# Schematic.net
KiCad netlist of a schematic drawn in EAGLE
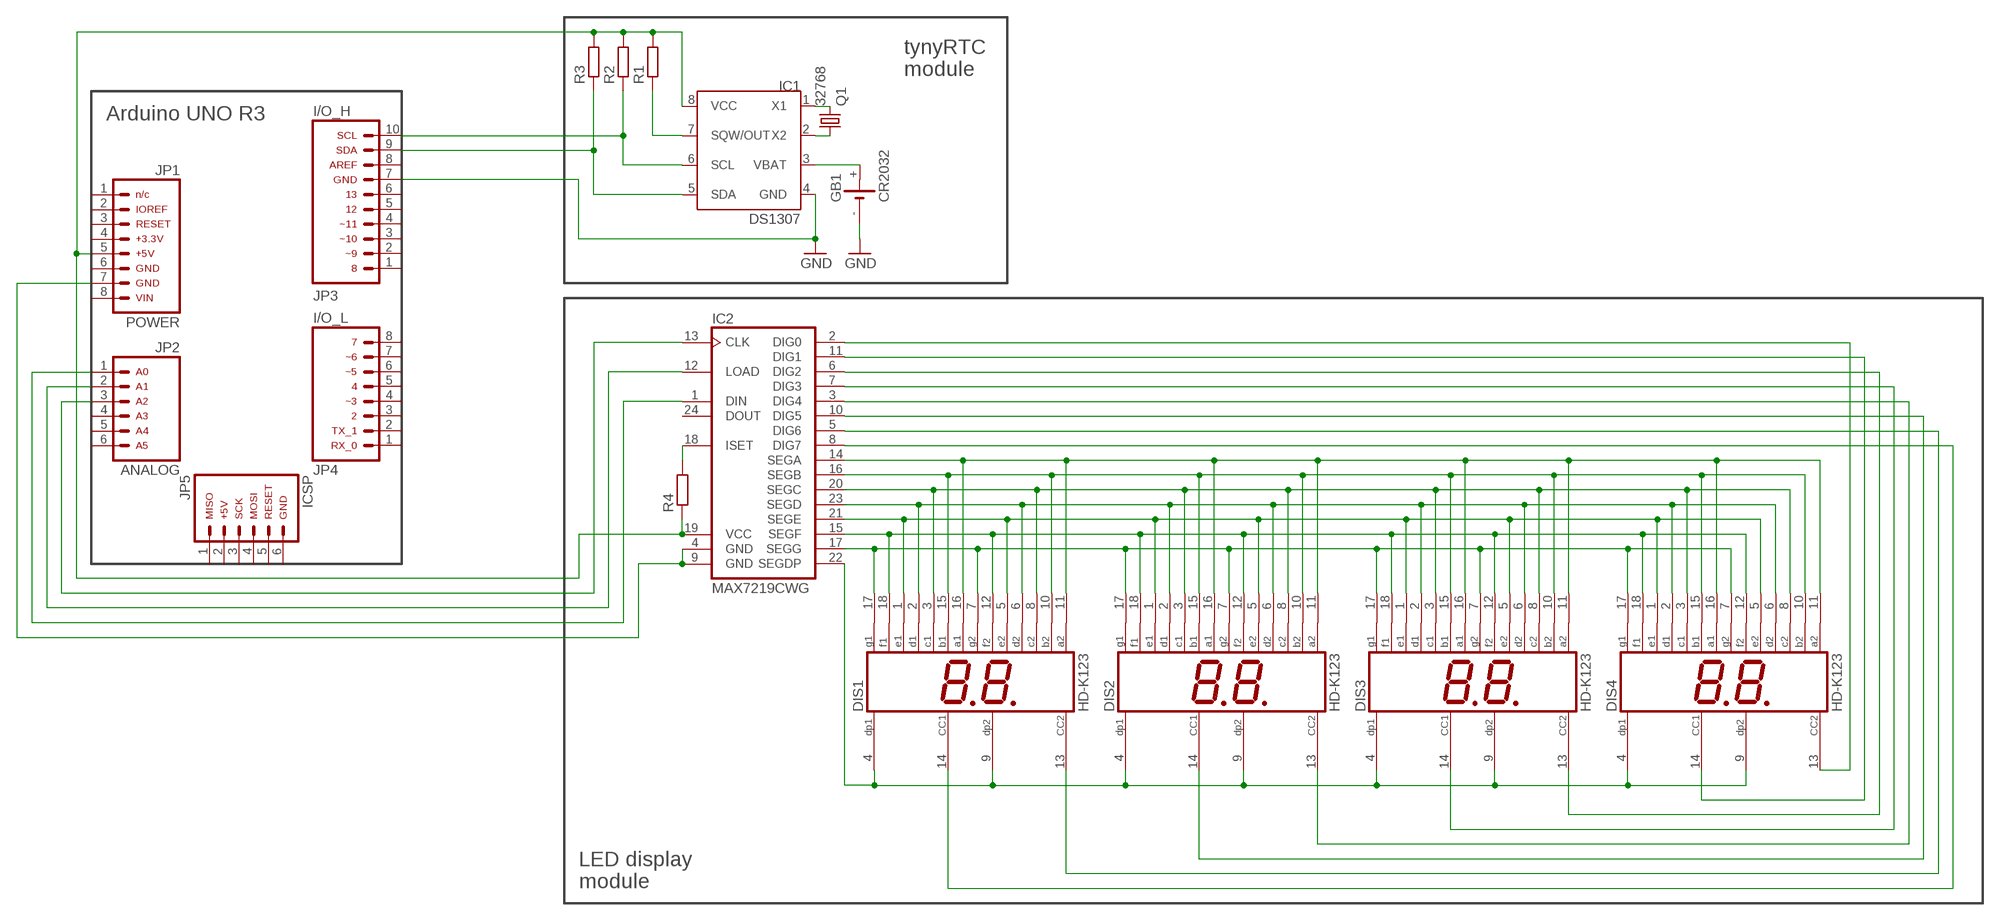
[diagram p0: schematic, sheet 1]

(export (version "E")
  (design (tool "Eeschema 10.0.6"))
  (components
    (comp (ref "DIS1")
      (value "HD-K123")
      (footprint "eagle-import:HDSP-R")
      (libsource (lib "eagle-import") (part "HD-K123"))
    )
    (comp (ref "DIS2")
      (value "HD-K123")
      (footprint "eagle-import:HDSP-R")
      (libsource (lib "eagle-import") (part "HD-K123"))
    )
    (comp (ref "DIS3")
      (value "HD-K123")
      (footprint "eagle-import:HDSP-R")
      (libsource (lib "eagle-import") (part "HD-K123"))
    )
    (comp (ref "DIS4")
      (value "HD-K123")
      (footprint "eagle-import:HDSP-R")
      (libsource (lib "eagle-import") (part "HD-K123"))
    )
    (comp (ref "GB1")
      (value "CR2032")
      (footprint "eagle-import:CR2032")
      (libsource (lib "eagle-import") (part "CR2032"))
    )
    (comp (ref "IC1")
      (value "DS1307")
      (footprint "eagle-import:SOIC-8")
      (libsource (lib "eagle-import") (part "DS1307"))
    )
    (comp (ref "IC2")
      (value "MAX7219CWG")
      (footprint "eagle-import:SO24W")
      (libsource (lib "eagle-import") (part "MAX7219WGC"))
    )
    (comp (ref "JP1")
      (value "ARDUINO_CONN-POWERSIP")
      (footprint "eagle-import:CONN-1X08")
      (libsource (lib "eagle-import") (part "ARDUINO_CONN-POWERSIP"))
    )
    (comp (ref "JP2")
      (value "ARDUINO_CONN-ANALOGSIP")
      (footprint "eagle-import:CONN-1X06")
      (libsource (lib "eagle-import") (part "ARDUINO_CONN-ANALOGSIP"))
    )
    (comp (ref "JP3")
      (value "ARDUINO_CONN-IO_HSIP")
      (footprint "eagle-import:CONN-1X10")
      (libsource (lib "eagle-import") (part "ARDUINO_CONN-IO_HSIP"))
    )
    (comp (ref "JP4")
      (value "ARDUINO_CONN-IO_LSIP")
      (footprint "eagle-import:CONN-1X08")
      (libsource (lib "eagle-import") (part "ARDUINO_CONN-IO_LSIP"))
    )
    (comp (ref "JP5")
      (value "ARDUINO_CONN-ICSP")
      (footprint "eagle-import:CONN-2X03")
      (libsource (lib "eagle-import") (part "ARDUINO_CONN-ICSP"))
    )
    (comp (ref "Q1")
      (value "32768")
      (footprint "eagle-import:TC26H")
      (libsource (lib "eagle-import") (part "CRYSTALTC26H"))
    )
    (comp (ref "R1")
      (value "R-EU_R0805")
      (footprint "eagle-import:R0805")
      (libsource (lib "eagle-import") (part "R-EU_R0805"))
    )
    (comp (ref "R2")
      (value "R-EU_R0805")
      (footprint "eagle-import:R0805")
      (libsource (lib "eagle-import") (part "R-EU_R0805"))
    )
    (comp (ref "R3")
      (value "R-EU_R0805")
      (footprint "eagle-import:R0805")
      (libsource (lib "eagle-import") (part "R-EU_R0805"))
    )
    (comp (ref "R4")
      (value "R-EU_R0805")
      (footprint "eagle-import:R0805")
      (libsource (lib "eagle-import") (part "R-EU_R0805"))
    )
  )
  (nets
    (net (code "1") (name "GND") (class "Default")
      (node (ref "GB1") (pin "-") (pinfunction "-_-") (pintype "passive"))
      (node (ref "IC1") (pin "4") (pinfunction "GND_4") (pintype "power_in"))
      (node (ref "JP3") (pin "7") (pinfunction "7_7") (pintype "passive"))
    )
    (net (code "2") (name "Net-(DIS1-A1)") (class "Default")
      (node (ref "DIS1") (pin "11") (pinfunction "A2_11") (pintype "passive"))
      (node (ref "DIS1") (pin "16") (pinfunction "A1_16") (pintype "passive"))
      (node (ref "DIS2") (pin "11") (pinfunction "A2_11") (pintype "passive"))
      (node (ref "DIS2") (pin "16") (pinfunction "A1_16") (pintype "passive"))
      (node (ref "DIS3") (pin "11") (pinfunction "A2_11") (pintype "passive"))
      (node (ref "DIS3") (pin "16") (pinfunction "A1_16") (pintype "passive"))
      (node (ref "DIS4") (pin "11") (pinfunction "A2_11") (pintype "passive"))
      (node (ref "DIS4") (pin "16") (pinfunction "A1_16") (pintype "passive"))
      (node (ref "IC2") (pin "14") (pinfunction "SEGA_14") (pintype "output"))
    )
    (net (code "3") (name "Net-(DIS1-B1)") (class "Default")
      (node (ref "DIS1") (pin "10") (pinfunction "B2_10") (pintype "passive"))
      (node (ref "DIS1") (pin "15") (pinfunction "B1_15") (pintype "passive"))
      (node (ref "DIS2") (pin "10") (pinfunction "B2_10") (pintype "passive"))
      (node (ref "DIS2") (pin "15") (pinfunction "B1_15") (pintype "passive"))
      (node (ref "DIS3") (pin "10") (pinfunction "B2_10") (pintype "passive"))
      (node (ref "DIS3") (pin "15") (pinfunction "B1_15") (pintype "passive"))
      (node (ref "DIS4") (pin "10") (pinfunction "B2_10") (pintype "passive"))
      (node (ref "DIS4") (pin "15") (pinfunction "B1_15") (pintype "passive"))
      (node (ref "IC2") (pin "16") (pinfunction "SEGB_16") (pintype "output"))
    )
    (net (code "4") (name "Net-(DIS1-C1)") (class "Default")
      (node (ref "DIS1") (pin "3") (pinfunction "C1_3") (pintype "passive"))
      (node (ref "DIS1") (pin "8") (pinfunction "C2_8") (pintype "passive"))
      (node (ref "DIS2") (pin "3") (pinfunction "C1_3") (pintype "passive"))
      (node (ref "DIS2") (pin "8") (pinfunction "C2_8") (pintype "passive"))
      (node (ref "DIS3") (pin "3") (pinfunction "C1_3") (pintype "passive"))
      (node (ref "DIS3") (pin "8") (pinfunction "C2_8") (pintype "passive"))
      (node (ref "DIS4") (pin "3") (pinfunction "C1_3") (pintype "passive"))
      (node (ref "DIS4") (pin "8") (pinfunction "C2_8") (pintype "passive"))
      (node (ref "IC2") (pin "20") (pinfunction "SEGC_20") (pintype "output"))
    )
    (net (code "5") (name "Net-(DIS1-CC1)") (class "Default")
      (node (ref "DIS1") (pin "14") (pinfunction "CC1_14") (pintype "passive"))
      (node (ref "IC2") (pin "8") (pinfunction "DIG7_8") (pintype "output"))
    )
    (net (code "6") (name "Net-(DIS1-CC2)") (class "Default")
      (node (ref "DIS1") (pin "13") (pinfunction "CC2_13") (pintype "passive"))
      (node (ref "IC2") (pin "5") (pinfunction "DIG6_5") (pintype "output"))
    )
    (net (code "7") (name "Net-(DIS1-D1)") (class "Default")
      (node (ref "DIS1") (pin "2") (pinfunction "D1_2") (pintype "passive"))
      (node (ref "DIS1") (pin "6") (pinfunction "D2_6") (pintype "passive"))
      (node (ref "DIS2") (pin "2") (pinfunction "D1_2") (pintype "passive"))
      (node (ref "DIS2") (pin "6") (pinfunction "D2_6") (pintype "passive"))
      (node (ref "DIS3") (pin "2") (pinfunction "D1_2") (pintype "passive"))
      (node (ref "DIS3") (pin "6") (pinfunction "D2_6") (pintype "passive"))
      (node (ref "DIS4") (pin "2") (pinfunction "D1_2") (pintype "passive"))
      (node (ref "DIS4") (pin "6") (pinfunction "D2_6") (pintype "passive"))
      (node (ref "IC2") (pin "23") (pinfunction "SEGD_23") (pintype "output"))
    )
    (net (code "8") (name "Net-(DIS1-DP1)") (class "Default")
      (node (ref "DIS1") (pin "4") (pinfunction "DP1_4") (pintype "passive"))
      (node (ref "DIS1") (pin "9") (pinfunction "DP2_9") (pintype "passive"))
      (node (ref "DIS2") (pin "4") (pinfunction "DP1_4") (pintype "passive"))
      (node (ref "DIS2") (pin "9") (pinfunction "DP2_9") (pintype "passive"))
      (node (ref "DIS3") (pin "4") (pinfunction "DP1_4") (pintype "passive"))
      (node (ref "DIS3") (pin "9") (pinfunction "DP2_9") (pintype "passive"))
      (node (ref "DIS4") (pin "4") (pinfunction "DP1_4") (pintype "passive"))
      (node (ref "DIS4") (pin "9") (pinfunction "DP2_9") (pintype "passive"))
      (node (ref "IC2") (pin "22") (pinfunction "SEGDP_22") (pintype "output"))
    )
    (net (code "9") (name "Net-(DIS1-E1)") (class "Default")
      (node (ref "DIS1") (pin "1") (pinfunction "E1_1") (pintype "passive"))
      (node (ref "DIS1") (pin "5") (pinfunction "E2_5") (pintype "passive"))
      (node (ref "DIS2") (pin "1") (pinfunction "E1_1") (pintype "passive"))
      (node (ref "DIS2") (pin "5") (pinfunction "E2_5") (pintype "passive"))
      (node (ref "DIS3") (pin "1") (pinfunction "E1_1") (pintype "passive"))
      (node (ref "DIS3") (pin "5") (pinfunction "E2_5") (pintype "passive"))
      (node (ref "DIS4") (pin "1") (pinfunction "E1_1") (pintype "passive"))
      (node (ref "DIS4") (pin "5") (pinfunction "E2_5") (pintype "passive"))
      (node (ref "IC2") (pin "21") (pinfunction "SEGE_21") (pintype "output"))
    )
    (net (code "10") (name "Net-(DIS1-F1)") (class "Default")
      (node (ref "DIS1") (pin "12") (pinfunction "F2_12") (pintype "passive"))
      (node (ref "DIS1") (pin "18") (pinfunction "F1_18") (pintype "passive"))
      (node (ref "DIS2") (pin "12") (pinfunction "F2_12") (pintype "passive"))
      (node (ref "DIS2") (pin "18") (pinfunction "F1_18") (pintype "passive"))
      (node (ref "DIS3") (pin "12") (pinfunction "F2_12") (pintype "passive"))
      (node (ref "DIS3") (pin "18") (pinfunction "F1_18") (pintype "passive"))
      (node (ref "DIS4") (pin "12") (pinfunction "F2_12") (pintype "passive"))
      (node (ref "DIS4") (pin "18") (pinfunction "F1_18") (pintype "passive"))
      (node (ref "IC2") (pin "15") (pinfunction "SEGF_15") (pintype "output"))
    )
    (net (code "11") (name "Net-(DIS1-G1)") (class "Default")
      (node (ref "DIS1") (pin "17") (pinfunction "G1_17") (pintype "passive"))
      (node (ref "DIS1") (pin "7") (pinfunction "G2_7") (pintype "passive"))
      (node (ref "DIS2") (pin "17") (pinfunction "G1_17") (pintype "passive"))
      (node (ref "DIS2") (pin "7") (pinfunction "G2_7") (pintype "passive"))
      (node (ref "DIS3") (pin "17") (pinfunction "G1_17") (pintype "passive"))
      (node (ref "DIS3") (pin "7") (pinfunction "G2_7") (pintype "passive"))
      (node (ref "DIS4") (pin "17") (pinfunction "G1_17") (pintype "passive"))
      (node (ref "DIS4") (pin "7") (pinfunction "G2_7") (pintype "passive"))
      (node (ref "IC2") (pin "17") (pinfunction "SEGG_17") (pintype "output"))
    )
    (net (code "12") (name "Net-(DIS2-CC1)") (class "Default")
      (node (ref "DIS2") (pin "14") (pinfunction "CC1_14") (pintype "passive"))
      (node (ref "IC2") (pin "10") (pinfunction "DIG5_10") (pintype "output"))
    )
    (net (code "13") (name "Net-(DIS2-CC2)") (class "Default")
      (node (ref "DIS2") (pin "13") (pinfunction "CC2_13") (pintype "passive"))
      (node (ref "IC2") (pin "3") (pinfunction "DIG4_3") (pintype "output"))
    )
    (net (code "14") (name "Net-(DIS3-CC1)") (class "Default")
      (node (ref "DIS3") (pin "14") (pinfunction "CC1_14") (pintype "passive"))
      (node (ref "IC2") (pin "7") (pinfunction "DIG3_7") (pintype "output"))
    )
    (net (code "15") (name "Net-(DIS3-CC2)") (class "Default")
      (node (ref "DIS3") (pin "13") (pinfunction "CC2_13") (pintype "passive"))
      (node (ref "IC2") (pin "6") (pinfunction "DIG2_6") (pintype "output"))
    )
    (net (code "16") (name "Net-(DIS4-CC1)") (class "Default")
      (node (ref "DIS4") (pin "14") (pinfunction "CC1_14") (pintype "passive"))
      (node (ref "IC2") (pin "11") (pinfunction "DIG1_11") (pintype "output"))
    )
    (net (code "17") (name "Net-(DIS4-CC2)") (class "Default")
      (node (ref "DIS4") (pin "13") (pinfunction "CC2_13") (pintype "passive"))
      (node (ref "IC2") (pin "2") (pinfunction "DIG0_2") (pintype "output"))
    )
    (net (code "18") (name "Net-(IC1-SCL)") (class "Default")
      (node (ref "IC1") (pin "6") (pinfunction "SCL_6") (pintype "input"))
      (node (ref "JP3") (pin "10") (pinfunction "10_10") (pintype "passive"))
      (node (ref "R2") (pin "1") (pinfunction "1_1") (pintype "passive"))
    )
    (net (code "19") (name "Net-(IC1-SDA)") (class "Default")
      (node (ref "IC1") (pin "5") (pinfunction "SDA_5") (pintype "bidirectional"))
      (node (ref "JP3") (pin "9") (pinfunction "9_9") (pintype "passive"))
      (node (ref "R3") (pin "1") (pinfunction "1_1") (pintype "passive"))
    )
    (net (code "20") (name "Net-(IC1-SQW{slash}OUT)") (class "Default")
      (node (ref "IC1") (pin "7") (pinfunction "SQW/OUT_7") (pintype "output"))
      (node (ref "R1") (pin "1") (pinfunction "1_1") (pintype "passive"))
    )
    (net (code "21") (name "Net-(IC1-VBAT)") (class "Default")
      (node (ref "GB1") (pin "+") (pinfunction "+_+") (pintype "passive"))
      (node (ref "IC1") (pin "3") (pinfunction "VBAT_3") (pintype "power_in"))
    )
    (net (code "22") (name "Net-(IC1-VCC)") (class "Default")
      (node (ref "IC1") (pin "8") (pinfunction "VCC_8") (pintype "power_in"))
      (node (ref "IC2") (pin "19") (pinfunction "VCC_19") (pintype "power_in"))
      (node (ref "JP1") (pin "5") (pinfunction "5_5") (pintype "passive"))
      (node (ref "R1") (pin "2") (pinfunction "2_2") (pintype "passive"))
      (node (ref "R2") (pin "2") (pinfunction "2_2") (pintype "passive"))
      (node (ref "R3") (pin "2") (pinfunction "2_2") (pintype "passive"))
      (node (ref "R4") (pin "1") (pinfunction "1_1") (pintype "passive"))
    )
    (net (code "23") (name "Net-(IC1-X1)") (class "Default")
      (node (ref "IC1") (pin "1") (pinfunction "X1_1") (pintype "input"))
      (node (ref "Q1") (pin "2") (pinfunction "2_2") (pintype "passive"))
    )
    (net (code "24") (name "Net-(IC1-X2)") (class "Default")
      (node (ref "IC1") (pin "2") (pinfunction "X2_2") (pintype "output"))
      (node (ref "Q1") (pin "1") (pinfunction "1_1") (pintype "passive"))
    )
    (net (code "25") (name "Net-(IC2-CLK)") (class "Default")
      (node (ref "IC2") (pin "13") (pinfunction "CLK_13") (pintype "input"))
      (node (ref "JP2") (pin "3") (pinfunction "3_3") (pintype "passive"))
    )
    (net (code "26") (name "Net-(IC2-DIN)") (class "Default")
      (node (ref "IC2") (pin "1") (pinfunction "DIN_1") (pintype "input"))
      (node (ref "JP2") (pin "1") (pinfunction "1_1") (pintype "passive"))
    )
    (net (code "27") (name "Net-(IC2-GND-Pad4)") (class "Default")
      (node (ref "IC2") (pin "4") (pinfunction "GND_4") (pintype "power_in"))
      (node (ref "IC2") (pin "9") (pinfunction "GND_9") (pintype "power_in"))
      (node (ref "JP1") (pin "7") (pinfunction "7_7") (pintype "passive"))
    )
    (net (code "28") (name "Net-(IC2-ISET)") (class "Default")
      (node (ref "IC2") (pin "18") (pinfunction "ISET_18") (pintype "input"))
      (node (ref "R4") (pin "2") (pinfunction "2_2") (pintype "passive"))
    )
    (net (code "29") (name "Net-(IC2-LOAD)") (class "Default")
      (node (ref "IC2") (pin "12") (pinfunction "LOAD_12") (pintype "input"))
      (node (ref "JP2") (pin "2") (pinfunction "2_2") (pintype "passive"))
    )
    (net (code "30") (name "unconnected-(IC2-DOUT-Pad24)") (class "Default")
      (node (ref "IC2") (pin "24") (pinfunction "DOUT_24") (pintype "output"))
    )
    (net (code "31") (name "unconnected-(JP1-Pad1)") (class "Default")
      (node (ref "JP1") (pin "1") (pinfunction "1_1") (pintype "passive"))
    )
    (net (code "32") (name "unconnected-(JP1-Pad2)") (class "Default")
      (node (ref "JP1") (pin "2") (pinfunction "2_2") (pintype "passive"))
    )
    (net (code "33") (name "unconnected-(JP1-Pad3)") (class "Default")
      (node (ref "JP1") (pin "3") (pinfunction "3_3") (pintype "passive"))
    )
    (net (code "34") (name "unconnected-(JP1-Pad4)") (class "Default")
      (node (ref "JP1") (pin "4") (pinfunction "4_4") (pintype "passive"))
    )
    (net (code "35") (name "unconnected-(JP1-Pad6)") (class "Default")
      (node (ref "JP1") (pin "6") (pinfunction "6_6") (pintype "passive"))
    )
    (net (code "36") (name "unconnected-(JP1-Pad8)") (class "Default")
      (node (ref "JP1") (pin "8") (pinfunction "8_8") (pintype "passive"))
    )
    (net (code "37") (name "unconnected-(JP2-Pad4)") (class "Default")
      (node (ref "JP2") (pin "4") (pinfunction "4_4") (pintype "passive"))
    )
    (net (code "38") (name "unconnected-(JP2-Pad5)") (class "Default")
      (node (ref "JP2") (pin "5") (pinfunction "5_5") (pintype "passive"))
    )
    (net (code "39") (name "unconnected-(JP2-Pad6)") (class "Default")
      (node (ref "JP2") (pin "6") (pinfunction "6_6") (pintype "passive"))
    )
    (net (code "40") (name "unconnected-(JP3-Pad1)") (class "Default")
      (node (ref "JP3") (pin "1") (pinfunction "1_1") (pintype "passive"))
    )
    (net (code "41") (name "unconnected-(JP3-Pad2)") (class "Default")
      (node (ref "JP3") (pin "2") (pinfunction "2_2") (pintype "passive"))
    )
    (net (code "42") (name "unconnected-(JP3-Pad3)") (class "Default")
      (node (ref "JP3") (pin "3") (pinfunction "3_3") (pintype "passive"))
    )
    (net (code "43") (name "unconnected-(JP3-Pad4)") (class "Default")
      (node (ref "JP3") (pin "4") (pinfunction "4_4") (pintype "passive"))
    )
    (net (code "44") (name "unconnected-(JP3-Pad5)") (class "Default")
      (node (ref "JP3") (pin "5") (pinfunction "5_5") (pintype "passive"))
    )
    (net (code "45") (name "unconnected-(JP3-Pad6)") (class "Default")
      (node (ref "JP3") (pin "6") (pinfunction "6_6") (pintype "passive"))
    )
    (net (code "46") (name "unconnected-(JP3-Pad8)") (class "Default")
      (node (ref "JP3") (pin "8") (pinfunction "8_8") (pintype "passive"))
    )
    (net (code "47") (name "unconnected-(JP4-Pad1)") (class "Default")
      (node (ref "JP4") (pin "1") (pinfunction "1_1") (pintype "passive"))
    )
    (net (code "48") (name "unconnected-(JP4-Pad2)") (class "Default")
      (node (ref "JP4") (pin "2") (pinfunction "2_2") (pintype "passive"))
    )
    (net (code "49") (name "unconnected-(JP4-Pad3)") (class "Default")
      (node (ref "JP4") (pin "3") (pinfunction "3_3") (pintype "passive"))
    )
    (net (code "50") (name "unconnected-(JP4-Pad4)") (class "Default")
      (node (ref "JP4") (pin "4") (pinfunction "4_4") (pintype "passive"))
    )
    (net (code "51") (name "unconnected-(JP4-Pad5)") (class "Default")
      (node (ref "JP4") (pin "5") (pinfunction "5_5") (pintype "passive"))
    )
    (net (code "52") (name "unconnected-(JP4-Pad6)") (class "Default")
      (node (ref "JP4") (pin "6") (pinfunction "6_6") (pintype "passive"))
    )
    (net (code "53") (name "unconnected-(JP4-Pad7)") (class "Default")
      (node (ref "JP4") (pin "7") (pinfunction "7_7") (pintype "passive"))
    )
    (net (code "54") (name "unconnected-(JP4-Pad8)") (class "Default")
      (node (ref "JP4") (pin "8") (pinfunction "8_8") (pintype "passive"))
    )
    (net (code "55") (name "unconnected-(JP5-Pad1)") (class "Default")
      (node (ref "JP5") (pin "1") (pinfunction "1_1") (pintype "passive"))
    )
    (net (code "56") (name "unconnected-(JP5-Pad2)") (class "Default")
      (node (ref "JP5") (pin "2") (pinfunction "2_2") (pintype "passive"))
    )
    (net (code "57") (name "unconnected-(JP5-Pad3)") (class "Default")
      (node (ref "JP5") (pin "3") (pinfunction "3_3") (pintype "passive"))
    )
    (net (code "58") (name "unconnected-(JP5-Pad4)") (class "Default")
      (node (ref "JP5") (pin "4") (pinfunction "4_4") (pintype "passive"))
    )
    (net (code "59") (name "unconnected-(JP5-Pad5)") (class "Default")
      (node (ref "JP5") (pin "5") (pinfunction "5_5") (pintype "passive"))
    )
    (net (code "60") (name "unconnected-(JP5-Pad6)") (class "Default")
      (node (ref "JP5") (pin "6") (pinfunction "6_6") (pintype "passive"))
    )
  )
)
